# SensorBoard_copy.net
KiCad netlist of a schematic drawn in EAGLE
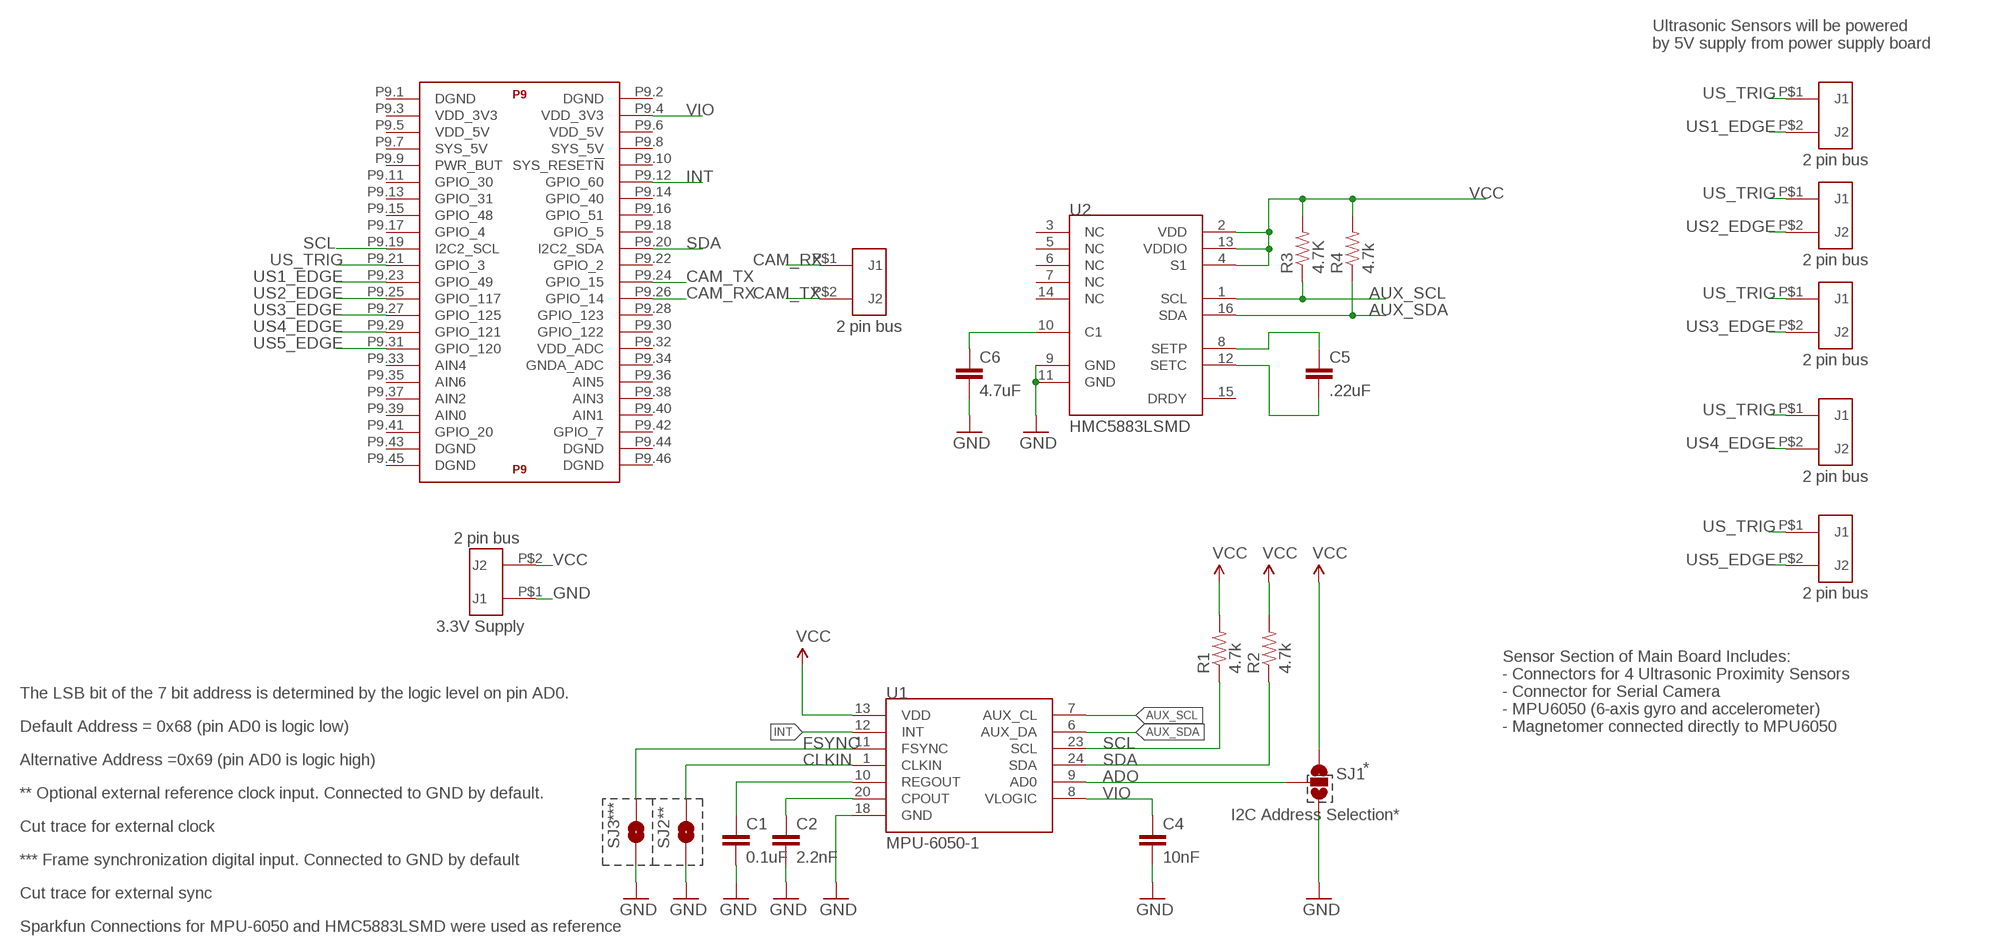
[diagram p0: schematic, sheet 1]

(export (version "E")
  (design (tool "Eeschema 10.0.6"))
  (components
    (comp (ref "C1")
      (value "0.1uF")
      (footprint "eagle-import:0603-CAP")
      (libsource (lib "eagle-import") (part "CAP0603-CAP"))
    )
    (comp (ref "C2")
      (value "2.2nF")
      (footprint "eagle-import:0603-CAP")
      (libsource (lib "eagle-import") (part "CAP0603-CAP"))
    )
    (comp (ref "C4")
      (value "10nF")
      (footprint "eagle-import:0603-CAP")
      (libsource (lib "eagle-import") (part "CAP0603-CAP"))
    )
    (comp (ref "C5")
      (value ".22uF")
      (footprint "eagle-import:0402-CAP")
      (libsource (lib "eagle-import") (part "CAP0402-CAP"))
    )
    (comp (ref "C6")
      (value "4.7uF")
      (footprint "eagle-import:0402-CAP")
      (libsource (lib "eagle-import") (part "CAP0402-CAP"))
    )
    (comp (ref "R1")
      (value "4.7k")
      (footprint "eagle-import:0603-RES")
      (libsource (lib "eagle-import") (part "RESISTOR0603-RES"))
    )
    (comp (ref "R2")
      (value "4.7k")
      (footprint "eagle-import:0603-RES")
      (libsource (lib "eagle-import") (part "RESISTOR0603-RES"))
    )
    (comp (ref "R3")
      (value "4.7K")
      (footprint "eagle-import:0402-RES")
      (libsource (lib "eagle-import") (part "RESISTOR0402-RES"))
    )
    (comp (ref "R4")
      (value "4.7k")
      (footprint "eagle-import:0402-RES")
      (libsource (lib "eagle-import") (part "RESISTOR0402-RES"))
    )
    (comp (ref "SJ1")
      (value "SOLDERJUMPER_2WAYPASTE2&3")
      (footprint "eagle-import:SJ_3_PASTE2&3")
      (libsource (lib "eagle-import") (part "SOLDERJUMPER_2WAYPASTE2&3"))
    )
    (comp (ref "SJ2")
      (value "SOLDERJUMPERTRACE")
      (footprint "eagle-import:SJ_2S-TRACE")
      (libsource (lib "eagle-import") (part "SOLDERJUMPERTRACE"))
    )
    (comp (ref "SJ3")
      (value "SOLDERJUMPERTRACE")
      (footprint "eagle-import:SJ_2S-TRACE")
      (libsource (lib "eagle-import") (part "SOLDERJUMPERTRACE"))
    )
    (comp (ref "U$1")
      (value "2PINBUS2HOLE")
      (footprint "eagle-import:2PINBUS")
      (libsource (lib "eagle-import") (part "2PINBUS2HOLE"))
    )
    (comp (ref "U$2")
      (value "BEAGLE_BONE_BLACK_CAPE")
      (footprint "eagle-import:BEAGLE_BONE_BLACK_CAPE")
      (libsource (lib "eagle-import") (part "BEAGLE_BONE_BLACK_CAPE"))
    )
    (comp (ref "U$3")
      (value "2PINBUS2HOLE")
      (footprint "eagle-import:2PINBUS")
      (libsource (lib "eagle-import") (part "2PINBUS2HOLE"))
    )
    (comp (ref "U$4")
      (value "2PINBUS2HOLE")
      (footprint "eagle-import:2PINBUS")
      (libsource (lib "eagle-import") (part "2PINBUS2HOLE"))
    )
    (comp (ref "U$6")
      (value "2PINBUS2HOLE")
      (footprint "eagle-import:2PINBUS")
      (libsource (lib "eagle-import") (part "2PINBUS2HOLE"))
    )
    (comp (ref "U$7")
      (value "2PINBUS2HOLE")
      (footprint "eagle-import:2PINBUS")
      (libsource (lib "eagle-import") (part "2PINBUS2HOLE"))
    )
    (comp (ref "U$8")
      (value "2PINBUS2HOLE")
      (footprint "eagle-import:2PINBUS")
      (libsource (lib "eagle-import") (part "2PINBUS2HOLE"))
    )
    (comp (ref "U$9")
      (value "2PINBUS2HOLE")
      (footprint "eagle-import:2PINBUS")
      (libsource (lib "eagle-import") (part "2PINBUS2HOLE"))
    )
    (comp (ref "U1")
      (value "MPU-6050-1")
      (footprint "eagle-import:QFN-24-4MM2")
      (libsource (lib "eagle-import") (part "MPU-6050-1"))
    )
    (comp (ref "U2")
      (value "HMC5883LSMD")
      (footprint "eagle-import:16LPCC")
      (libsource (lib "eagle-import") (part "HMC5883LSMD"))
    )
  )
  (nets
    (net (code "1") (name "/ADO") (class "Default")
      (node (ref "SJ1") (pin "2") (pinfunction "2_2") (pintype "passive"))
      (node (ref "U1") (pin "9") (pinfunction "AD0_9") (pintype "bidirectional"))
    )
    (net (code "2") (name "/CAM_RX") (class "Default")
      (node (ref "U$2") (pin "P9.26") (pinfunction "GPIO_14_P9.26") (pintype "bidirectional"))
      (node (ref "U$3") (pin "P$1") (pinfunction "J1_P$1") (pintype "bidirectional"))
    )
    (net (code "3") (name "/CAM_TX") (class "Default")
      (node (ref "U$2") (pin "P9.24") (pinfunction "GPIO_15_P9.24") (pintype "bidirectional"))
      (node (ref "U$3") (pin "P$2") (pinfunction "J2_P$2") (pintype "bidirectional"))
    )
    (net (code "4") (name "/CLKIN") (class "Default")
      (node (ref "SJ2") (pin "2") (pinfunction "2_2") (pintype "passive"))
      (node (ref "U1") (pin "1") (pinfunction "CLKIN_1") (pintype "bidirectional"))
    )
    (net (code "5") (name "/FSYNC") (class "Default")
      (node (ref "SJ3") (pin "2") (pinfunction "2_2") (pintype "passive"))
      (node (ref "U1") (pin "11") (pinfunction "FSYNC_11") (pintype "bidirectional"))
    )
    (net (code "6") (name "/SCL") (class "Default")
      (node (ref "R1") (pin "1") (pinfunction "1_1") (pintype "passive"))
      (node (ref "U$2") (pin "P9.19") (pinfunction "I2C2_SCL_P9.19") (pintype "bidirectional"))
      (node (ref "U1") (pin "23") (pinfunction "SCL_23") (pintype "bidirectional"))
    )
    (net (code "7") (name "/SDA") (class "Default")
      (node (ref "R2") (pin "1") (pinfunction "1_1") (pintype "passive"))
      (node (ref "U$2") (pin "P9.20") (pinfunction "I2C2_SDA_P9.20") (pintype "bidirectional"))
      (node (ref "U1") (pin "24") (pinfunction "SDA_24") (pintype "bidirectional"))
    )
    (net (code "8") (name "/US1_EDGE") (class "Default")
      (node (ref "U$2") (pin "P9.23") (pinfunction "GPIO_49_P9.23") (pintype "bidirectional"))
      (node (ref "U$8") (pin "P$2") (pinfunction "J2_P$2") (pintype "bidirectional"))
    )
    (net (code "9") (name "/US2_EDGE") (class "Default")
      (node (ref "U$2") (pin "P9.25") (pinfunction "GPIO_117_P9.25") (pintype "bidirectional"))
      (node (ref "U$7") (pin "P$2") (pinfunction "J2_P$2") (pintype "bidirectional"))
    )
    (net (code "10") (name "/US3_EDGE") (class "Default")
      (node (ref "U$2") (pin "P9.27") (pinfunction "GPIO_125_P9.27") (pintype "bidirectional"))
      (node (ref "U$6") (pin "P$2") (pinfunction "J2_P$2") (pintype "bidirectional"))
    )
    (net (code "11") (name "/US4_EDGE") (class "Default")
      (node (ref "U$2") (pin "P9.29") (pinfunction "GPIO_121_P9.29") (pintype "bidirectional"))
      (node (ref "U$4") (pin "P$2") (pinfunction "J2_P$2") (pintype "bidirectional"))
    )
    (net (code "12") (name "/US5_EDGE") (class "Default")
      (node (ref "U$1") (pin "P$2") (pinfunction "J2_P$2") (pintype "bidirectional"))
      (node (ref "U$2") (pin "P9.31") (pinfunction "GPIO_120_P9.31") (pintype "bidirectional"))
    )
    (net (code "13") (name "/US_TRIG") (class "Default")
      (node (ref "U$1") (pin "P$1") (pinfunction "J1_P$1") (pintype "bidirectional"))
      (node (ref "U$2") (pin "P9.21") (pinfunction "GPIO_3_P9.21") (pintype "bidirectional"))
      (node (ref "U$4") (pin "P$1") (pinfunction "J1_P$1") (pintype "bidirectional"))
      (node (ref "U$6") (pin "P$1") (pinfunction "J1_P$1") (pintype "bidirectional"))
      (node (ref "U$7") (pin "P$1") (pinfunction "J1_P$1") (pintype "bidirectional"))
      (node (ref "U$8") (pin "P$1") (pinfunction "J1_P$1") (pintype "bidirectional"))
    )
    (net (code "14") (name "/VIO") (class "Default")
      (node (ref "C4") (pin "1") (pinfunction "1_1") (pintype "passive"))
      (node (ref "U$2") (pin "P9.4") (pinfunction "VDD_3V3_P9.4") (pintype "bidirectional"))
      (node (ref "U1") (pin "8") (pinfunction "VLOGIC_8") (pintype "bidirectional"))
    )
    (net (code "15") (name "AUX_SCL") (class "Default")
      (node (ref "R3") (pin "1") (pinfunction "1_1") (pintype "passive"))
      (node (ref "U1") (pin "7") (pinfunction "AUX_CL_7") (pintype "bidirectional"))
      (node (ref "U2") (pin "1") (pinfunction "SCL_1") (pintype "bidirectional"))
    )
    (net (code "16") (name "AUX_SDA") (class "Default")
      (node (ref "R4") (pin "1") (pinfunction "1_1") (pintype "passive"))
      (node (ref "U1") (pin "6") (pinfunction "AUX_DA_6") (pintype "bidirectional"))
      (node (ref "U2") (pin "16") (pinfunction "SDA_16") (pintype "bidirectional"))
    )
    (net (code "17") (name "GND") (class "Default")
      (node (ref "C1") (pin "2") (pinfunction "2_2") (pintype "passive"))
      (node (ref "C2") (pin "2") (pinfunction "2_2") (pintype "passive"))
      (node (ref "C4") (pin "2") (pinfunction "2_2") (pintype "passive"))
      (node (ref "C6") (pin "2") (pinfunction "2_2") (pintype "passive"))
      (node (ref "SJ1") (pin "3") (pinfunction "3_3") (pintype "passive"))
      (node (ref "SJ2") (pin "1") (pinfunction "1_1") (pintype "passive"))
      (node (ref "SJ3") (pin "1") (pinfunction "1_1") (pintype "passive"))
      (node (ref "U$9") (pin "P$1") (pinfunction "J1_P$1") (pintype "bidirectional"))
      (node (ref "U1") (pin "18") (pinfunction "GND_18") (pintype "bidirectional"))
      (node (ref "U2") (pin "11") (pinfunction "GND_11") (pintype "bidirectional"))
      (node (ref "U2") (pin "9") (pinfunction "GND_9") (pintype "bidirectional"))
    )
    (net (code "18") (name "INT") (class "Default")
      (node (ref "U$2") (pin "P9.12") (pinfunction "GPIO_60_P9.12") (pintype "bidirectional"))
      (node (ref "U1") (pin "12") (pinfunction "INT_12") (pintype "bidirectional"))
    )
    (net (code "19") (name "Net-(U1-CPOUT)") (class "Default")
      (node (ref "C2") (pin "1") (pinfunction "1_1") (pintype "passive"))
      (node (ref "U1") (pin "20") (pinfunction "CPOUT_20") (pintype "bidirectional"))
    )
    (net (code "20") (name "Net-(U1-REGOUT)") (class "Default")
      (node (ref "C1") (pin "1") (pinfunction "1_1") (pintype "passive"))
      (node (ref "U1") (pin "10") (pinfunction "REGOUT_10") (pintype "bidirectional"))
    )
    (net (code "21") (name "Net-(U2-C1)") (class "Default")
      (node (ref "C6") (pin "1") (pinfunction "1_1") (pintype "passive"))
      (node (ref "U2") (pin "10") (pinfunction "C1_10") (pintype "bidirectional"))
    )
    (net (code "22") (name "Net-(U2-SETC)") (class "Default")
      (node (ref "C5") (pin "2") (pinfunction "2_2") (pintype "passive"))
      (node (ref "U2") (pin "12") (pinfunction "SETC_12") (pintype "bidirectional"))
    )
    (net (code "23") (name "Net-(U2-SETP)") (class "Default")
      (node (ref "C5") (pin "1") (pinfunction "1_1") (pintype "passive"))
      (node (ref "U2") (pin "8") (pinfunction "SETP_8") (pintype "bidirectional"))
    )
    (net (code "24") (name "VCC") (class "Default")
      (node (ref "R1") (pin "2") (pinfunction "2_2") (pintype "passive"))
      (node (ref "R2") (pin "2") (pinfunction "2_2") (pintype "passive"))
      (node (ref "R3") (pin "2") (pinfunction "2_2") (pintype "passive"))
      (node (ref "R4") (pin "2") (pinfunction "2_2") (pintype "passive"))
      (node (ref "SJ1") (pin "1") (pinfunction "1_1") (pintype "passive"))
      (node (ref "U$9") (pin "P$2") (pinfunction "J2_P$2") (pintype "bidirectional"))
      (node (ref "U1") (pin "13") (pinfunction "VDD_13") (pintype "bidirectional"))
      (node (ref "U2") (pin "13") (pinfunction "VDDIO_13") (pintype "bidirectional"))
      (node (ref "U2") (pin "2") (pinfunction "VDD_2") (pintype "bidirectional"))
      (node (ref "U2") (pin "4") (pinfunction "S1_4") (pintype "bidirectional"))
    )
    (net (code "25") (name "unconnected-(U$2B-AIN0-PadP9.39)") (class "Default")
      (node (ref "U$2") (pin "P9.39") (pinfunction "AIN0_P9.39") (pintype "bidirectional"))
    )
    (net (code "26") (name "unconnected-(U$2B-AIN1-PadP9.40)") (class "Default")
      (node (ref "U$2") (pin "P9.40") (pinfunction "AIN1_P9.40") (pintype "bidirectional"))
    )
    (net (code "27") (name "unconnected-(U$2B-AIN2-PadP9.37)") (class "Default")
      (node (ref "U$2") (pin "P9.37") (pinfunction "AIN2_P9.37") (pintype "bidirectional"))
    )
    (net (code "28") (name "unconnected-(U$2B-AIN3-PadP9.38)") (class "Default")
      (node (ref "U$2") (pin "P9.38") (pinfunction "AIN3_P9.38") (pintype "bidirectional"))
    )
    (net (code "29") (name "unconnected-(U$2B-AIN4-PadP9.33)") (class "Default")
      (node (ref "U$2") (pin "P9.33") (pinfunction "AIN4_P9.33") (pintype "bidirectional"))
    )
    (net (code "30") (name "unconnected-(U$2B-AIN5-PadP9.36)") (class "Default")
      (node (ref "U$2") (pin "P9.36") (pinfunction "AIN5_P9.36") (pintype "bidirectional"))
    )
    (net (code "31") (name "unconnected-(U$2B-AIN6-PadP9.35)") (class "Default")
      (node (ref "U$2") (pin "P9.35") (pinfunction "AIN6_P9.35") (pintype "bidirectional"))
    )
    (net (code "32") (name "unconnected-(U$2B-DGND-PadP9.1)") (class "Default")
      (node (ref "U$2") (pin "P9.1") (pinfunction "DGND_P9.1") (pintype "bidirectional"))
    )
    (net (code "33") (name "unconnected-(U$2B-DGND-PadP9.2)") (class "Default")
      (node (ref "U$2") (pin "P9.2") (pinfunction "DGND_P9.2") (pintype "bidirectional"))
    )
    (net (code "34") (name "unconnected-(U$2B-DGND-PadP9.43)") (class "Default")
      (node (ref "U$2") (pin "P9.43") (pinfunction "DGND_P9.43") (pintype "bidirectional"))
    )
    (net (code "35") (name "unconnected-(U$2B-DGND-PadP9.44)") (class "Default")
      (node (ref "U$2") (pin "P9.44") (pinfunction "DGND_P9.44") (pintype "bidirectional"))
    )
    (net (code "36") (name "unconnected-(U$2B-DGND-PadP9.45)") (class "Default")
      (node (ref "U$2") (pin "P9.45") (pinfunction "DGND_P9.45") (pintype "bidirectional"))
    )
    (net (code "37") (name "unconnected-(U$2B-DGND-PadP9.46)") (class "Default")
      (node (ref "U$2") (pin "P9.46") (pinfunction "DGND_P9.46") (pintype "bidirectional"))
    )
    (net (code "38") (name "unconnected-(U$2B-GNDA_ADC-PadP9.34)") (class "Default")
      (node (ref "U$2") (pin "P9.34") (pinfunction "GNDA_ADC_P9.34") (pintype "bidirectional"))
    )
    (net (code "39") (name "unconnected-(U$2B-GPIO_2-PadP9.22)") (class "Default")
      (node (ref "U$2") (pin "P9.22") (pinfunction "GPIO_2_P9.22") (pintype "bidirectional"))
    )
    (net (code "40") (name "unconnected-(U$2B-GPIO_4-PadP9.17)") (class "Default")
      (node (ref "U$2") (pin "P9.17") (pinfunction "GPIO_4_P9.17") (pintype "bidirectional"))
    )
    (net (code "41") (name "unconnected-(U$2B-GPIO_5-PadP9.18)") (class "Default")
      (node (ref "U$2") (pin "P9.18") (pinfunction "GPIO_5_P9.18") (pintype "bidirectional"))
    )
    (net (code "42") (name "unconnected-(U$2B-GPIO_7-PadP9.42)") (class "Default")
      (node (ref "U$2") (pin "P9.42") (pinfunction "GPIO_7_P9.42") (pintype "bidirectional"))
    )
    (net (code "43") (name "unconnected-(U$2B-GPIO_20-PadP9.41)") (class "Default")
      (node (ref "U$2") (pin "P9.41") (pinfunction "GPIO_20_P9.41") (pintype "bidirectional"))
    )
    (net (code "44") (name "unconnected-(U$2B-GPIO_30-PadP9.11)") (class "Default")
      (node (ref "U$2") (pin "P9.11") (pinfunction "GPIO_30_P9.11") (pintype "bidirectional"))
    )
    (net (code "45") (name "unconnected-(U$2B-GPIO_31-PadP9.13)") (class "Default")
      (node (ref "U$2") (pin "P9.13") (pinfunction "GPIO_31_P9.13") (pintype "bidirectional"))
    )
    (net (code "46") (name "unconnected-(U$2B-GPIO_40-PadP9.14)") (class "Default")
      (node (ref "U$2") (pin "P9.14") (pinfunction "GPIO_40_P9.14") (pintype "bidirectional"))
    )
    (net (code "47") (name "unconnected-(U$2B-GPIO_48-PadP9.15)") (class "Default")
      (node (ref "U$2") (pin "P9.15") (pinfunction "GPIO_48_P9.15") (pintype "bidirectional"))
    )
    (net (code "48") (name "unconnected-(U$2B-GPIO_51-PadP9.16)") (class "Default")
      (node (ref "U$2") (pin "P9.16") (pinfunction "GPIO_51_P9.16") (pintype "bidirectional"))
    )
    (net (code "49") (name "unconnected-(U$2B-GPIO_122-PadP9.30)") (class "Default")
      (node (ref "U$2") (pin "P9.30") (pinfunction "GPIO_122_P9.30") (pintype "bidirectional"))
    )
    (net (code "50") (name "unconnected-(U$2B-GPIO_123-PadP9.28)") (class "Default")
      (node (ref "U$2") (pin "P9.28") (pinfunction "GPIO_123_P9.28") (pintype "bidirectional"))
    )
    (net (code "51") (name "unconnected-(U$2B-PWR_BUT-PadP9.9)") (class "Default")
      (node (ref "U$2") (pin "P9.9") (pinfunction "PWR_BUT_P9.9") (pintype "bidirectional"))
    )
    (net (code "52") (name "unconnected-(U$2B-SYS_5V-PadP9.7)") (class "Default")
      (node (ref "U$2") (pin "P9.7") (pinfunction "SYS_5V_P9.7") (pintype "bidirectional"))
    )
    (net (code "53") (name "unconnected-(U$2B-SYS_5V-PadP9.8)") (class "Default")
      (node (ref "U$2") (pin "P9.8") (pinfunction "SYS_5V_P9.8") (pintype "bidirectional"))
    )
    (net (code "54") (name "unconnected-(U$2B-SYS_RESET~{N}-PadP9.10)") (class "Default")
      (node (ref "U$2") (pin "P9.10") (pinfunction "SYS_RESET~{N}_P9.10") (pintype "bidirectional"))
    )
    (net (code "55") (name "unconnected-(U$2B-VDD_3V3-PadP9.3)") (class "Default")
      (node (ref "U$2") (pin "P9.3") (pinfunction "VDD_3V3_P9.3") (pintype "bidirectional"))
    )
    (net (code "56") (name "unconnected-(U$2B-VDD_5V-PadP9.5)") (class "Default")
      (node (ref "U$2") (pin "P9.5") (pinfunction "VDD_5V_P9.5") (pintype "bidirectional"))
    )
    (net (code "57") (name "unconnected-(U$2B-VDD_5V-PadP9.6)") (class "Default")
      (node (ref "U$2") (pin "P9.6") (pinfunction "VDD_5V_P9.6") (pintype "bidirectional"))
    )
    (net (code "58") (name "unconnected-(U$2B-VDD_ADC-PadP9.32)") (class "Default")
      (node (ref "U$2") (pin "P9.32") (pinfunction "VDD_ADC_P9.32") (pintype "bidirectional"))
    )
    (net (code "59") (name "unconnected-(U2-DRDY-Pad15)") (class "Default")
      (node (ref "U2") (pin "15") (pinfunction "DRDY_15") (pintype "bidirectional"))
    )
    (net (code "60") (name "unconnected-(U2-NC-Pad3)") (class "Default")
      (node (ref "U2") (pin "3") (pinfunction "NC_3") (pintype "bidirectional"))
    )
    (net (code "61") (name "unconnected-(U2-NC-Pad5)") (class "Default")
      (node (ref "U2") (pin "5") (pinfunction "NC_5") (pintype "bidirectional"))
    )
    (net (code "62") (name "unconnected-(U2-NC-Pad6)") (class "Default")
      (node (ref "U2") (pin "6") (pinfunction "NC_6") (pintype "bidirectional"))
    )
    (net (code "63") (name "unconnected-(U2-NC-Pad7)") (class "Default")
      (node (ref "U2") (pin "7") (pinfunction "NC_7") (pintype "bidirectional"))
    )
    (net (code "64") (name "unconnected-(U2-NC-Pad14)") (class "Default")
      (node (ref "U2") (pin "14") (pinfunction "NC_14") (pintype "bidirectional"))
    )
  )
)
